# tes1.net
KiCad netlist of a schematic drawn in EAGLE
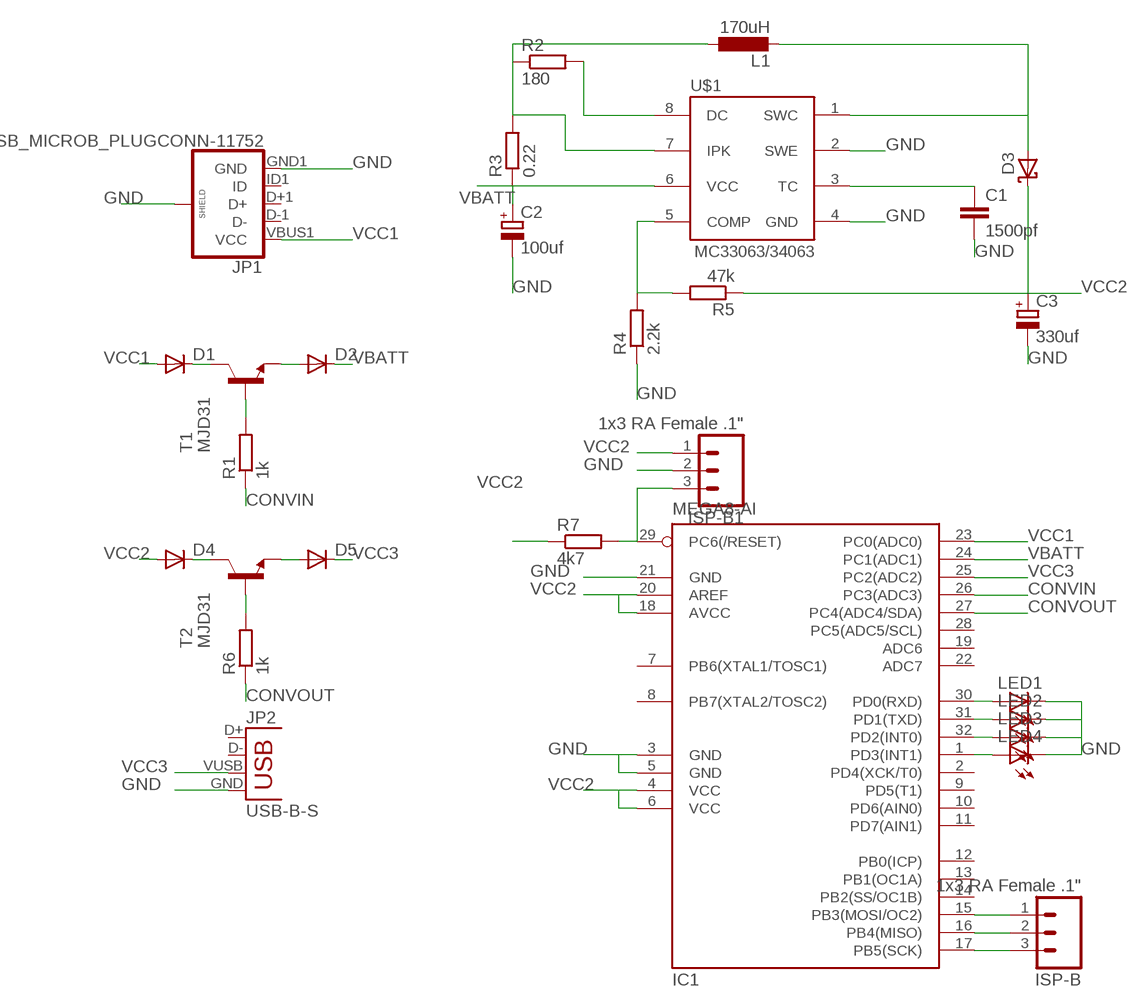
[diagram p0: schematic, sheet 1]

(export (version "E")
  (design (tool "Eeschema 10.0.6"))
  (components
    (comp (ref "C1")
      (value "1500pf")
      (footprint "eagle-import:C1206")
      (libsource (lib "eagle-import") (part "C-EUC1206"))
    )
    (comp (ref "C2")
      (value "100uf")
      (footprint "eagle-import:153CLV-1014")
      (libsource (lib "eagle-import") (part "CPOL-EU153CLV-1014"))
    )
    (comp (ref "C3")
      (value "330uf")
      (footprint "eagle-import:153CLV-1014")
      (libsource (lib "eagle-import") (part "CPOL-EU153CLV-1014"))
    )
    (comp (ref "D1")
      (value "DIODE-SMC")
      (footprint "eagle-import:SMC")
      (libsource (lib "eagle-import") (part "DIODE-SMC"))
    )
    (comp (ref "D2")
      (value "DIODE-SMC")
      (footprint "eagle-import:SMC")
      (libsource (lib "eagle-import") (part "DIODE-SMC"))
    )
    (comp (ref "D3")
      (value "SCHOTTKY-DIODEF126Z12")
      (footprint "eagle-import:F126Z12")
      (libsource (lib "eagle-import") (part "SCHOTTKY-DIODEF126Z12"))
    )
    (comp (ref "D4")
      (value "DIODE-SMC")
      (footprint "eagle-import:SMC")
      (libsource (lib "eagle-import") (part "DIODE-SMC"))
    )
    (comp (ref "D5")
      (value "DIODE-SMC")
      (footprint "eagle-import:SMC")
      (libsource (lib "eagle-import") (part "DIODE-SMC"))
    )
    (comp (ref "IC1")
      (value "MEGA8-AI")
      (footprint "eagle-import:TQFP32-08")
      (fields (field (name "MPN") "ATMEGA8-16AU"))
      (libsource (lib "eagle-import") (part "MEGA8-AI"))
    )
    (comp (ref "ISP-B")
      (value "1x3 RA Female .1\"")
      (footprint "eagle-import:1X03_SMD_RA_FEMALE")
      (libsource (lib "eagle-import") (part "M03SMD_RA_FEMALE"))
    )
    (comp (ref "ISP-B1")
      (value "1x3 RA Female .1\"")
      (footprint "eagle-import:1X03_SMD_RA_FEMALE")
      (libsource (lib "eagle-import") (part "M03SMD_RA_FEMALE"))
    )
    (comp (ref "JP1")
      (value "USB_MICROB_PLUGCONN-11752")
      (footprint "eagle-import:USB-B-MICRO-SMD_V03")
      (libsource (lib "eagle-import") (part "USB_MICROB_PLUGCONN-11752"))
    )
    (comp (ref "JP2")
      (value "USB-B-S")
      (footprint "eagle-import:USB-B-SMT")
      (libsource (lib "eagle-import") (part "USB-B-S"))
    )
    (comp (ref "L1")
      (value "170uH")
      (footprint "eagle-import:L5650M")
      (libsource (lib "eagle-import") (part "L-EUL5650M"))
    )
    (comp (ref "LED1")
      (value "LEDSML1206")
      (footprint "eagle-import:SML1206")
      (libsource (lib "eagle-import") (part "LEDSML1206"))
    )
    (comp (ref "LED2")
      (value "LEDSML1206")
      (footprint "eagle-import:SML1206")
      (libsource (lib "eagle-import") (part "LEDSML1206"))
    )
    (comp (ref "LED3")
      (value "LEDSML1206")
      (footprint "eagle-import:SML1206")
      (libsource (lib "eagle-import") (part "LEDSML1206"))
    )
    (comp (ref "LED4")
      (value "LEDSML1206")
      (footprint "eagle-import:SML1206")
      (libsource (lib "eagle-import") (part "LEDSML1206"))
    )
    (comp (ref "R1")
      (value "1k")
      (footprint "eagle-import:R1206")
      (libsource (lib "eagle-import") (part "R-EU_R1206"))
    )
    (comp (ref "R2")
      (value "180")
      (footprint "eagle-import:R1206")
      (libsource (lib "eagle-import") (part "resistor_R-EU_R1206"))
    )
    (comp (ref "R3")
      (value "0.22")
      (footprint "eagle-import:R1206")
      (libsource (lib "eagle-import") (part "resistor_R-EU_R1206"))
    )
    (comp (ref "R4")
      (value "2.2k")
      (footprint "eagle-import:R1206")
      (libsource (lib "eagle-import") (part "resistor_R-EU_R1206"))
    )
    (comp (ref "R5")
      (value "47k")
      (footprint "eagle-import:R1206")
      (libsource (lib "eagle-import") (part "resistor_R-EU_R1206"))
    )
    (comp (ref "R6")
      (value "1k")
      (footprint "eagle-import:R1206")
      (libsource (lib "eagle-import") (part "R-EU_R1206"))
    )
    (comp (ref "R7")
      (value "4k7")
      (footprint "eagle-import:R1206")
      (libsource (lib "eagle-import") (part "R-EU_R1206"))
    )
    (comp (ref "T1")
      (value "MJD31")
      (footprint "eagle-import:DPAK")
      (libsource (lib "eagle-import") (part "MJD31"))
    )
    (comp (ref "T2")
      (value "MJD31")
      (footprint "eagle-import:DPAK")
      (libsource (lib "eagle-import") (part "MJD31"))
    )
    (comp (ref "U$1")
      (value "MC33063/MC34063D")
      (footprint "eagle-import:SO08")
      (libsource (lib "eagle-import") (part "MC33063/MC34063D"))
    )
  )
  (nets
    (net (code "1") (name "/CONVIN") (class "Default")
      (node (ref "IC1") (pin "26") (pinfunction "PC3(ADC3)_26") (pintype "bidirectional"))
      (node (ref "R1") (pin "1") (pinfunction "1_1") (pintype "passive"))
    )
    (net (code "2") (name "/CONVOUT") (class "Default")
      (node (ref "IC1") (pin "27") (pinfunction "PC4(ADC4/SDA)_27") (pintype "bidirectional"))
      (node (ref "R6") (pin "1") (pinfunction "1_1") (pintype "passive"))
    )
    (net (code "3") (name "/GND") (class "Default")
      (node (ref "C1") (pin "2") (pinfunction "2_2") (pintype "passive"))
      (node (ref "C2") (pin "-") (pinfunction "-_-") (pintype "passive"))
      (node (ref "C3") (pin "-") (pinfunction "-_-") (pintype "passive"))
      (node (ref "IC1") (pin "21") (pinfunction "GND_21") (pintype "power_in"))
      (node (ref "IC1") (pin "3") (pinfunction "GND_3") (pintype "power_in"))
      (node (ref "IC1") (pin "5") (pinfunction "GND_5") (pintype "power_in"))
      (node (ref "ISP-B1") (pin "2") (pinfunction "2_2") (pintype "passive"))
      (node (ref "JP1") (pin "GND1") (pinfunction "GND_GND1") (pintype "bidirectional"))
      (node (ref "JP1") (pin "SHIELD1") (pinfunction "SHIELD_SHIELD1") (pintype "bidirectional"))
      (node (ref "JP1") (pin "SHIELD2") (pinfunction "SHIELD_SHIELD2") (pintype "bidirectional"))
      (node (ref "JP1") (pin "SHIELD3") (pinfunction "SHIELD_SHIELD3") (pintype "bidirectional"))
      (node (ref "JP2") (pin "GND") (pinfunction "GND_GND") (pintype "bidirectional"))
      (node (ref "LED1") (pin "C") (pinfunction "C_C") (pintype "passive"))
      (node (ref "LED2") (pin "C") (pinfunction "C_C") (pintype "passive"))
      (node (ref "LED3") (pin "C") (pinfunction "C_C") (pintype "passive"))
      (node (ref "LED4") (pin "C") (pinfunction "C_C") (pintype "passive"))
      (node (ref "R4") (pin "1") (pinfunction "1_1") (pintype "passive"))
      (node (ref "U$1") (pin "2") (pinfunction "SWE_2") (pintype "input"))
      (node (ref "U$1") (pin "4") (pinfunction "GND_4") (pintype "power_in"))
    )
    (net (code "4") (name "/VBATT") (class "Default")
      (node (ref "C2") (pin "+") (pinfunction "+_+") (pintype "passive"))
      (node (ref "D2") (pin "C") (pinfunction "C_C") (pintype "passive"))
      (node (ref "IC1") (pin "24") (pinfunction "PC1(ADC1)_24") (pintype "bidirectional"))
      (node (ref "R3") (pin "1") (pinfunction "1_1") (pintype "passive"))
      (node (ref "U$1") (pin "6") (pinfunction "VCC_6") (pintype "power_in"))
    )
    (net (code "5") (name "/VCC1") (class "Default")
      (node (ref "D1") (pin "A") (pinfunction "A_A") (pintype "passive"))
      (node (ref "IC1") (pin "23") (pinfunction "PC0(ADC0)_23") (pintype "bidirectional"))
      (node (ref "JP1") (pin "VBUS1") (pinfunction "VCC_VBUS1") (pintype "bidirectional"))
    )
    (net (code "6") (name "/VCC2") (class "Default")
      (node (ref "C3") (pin "+") (pinfunction "+_+") (pintype "passive"))
      (node (ref "D3") (pin "C") (pinfunction "C_C") (pintype "passive"))
      (node (ref "D4") (pin "A") (pinfunction "A_A") (pintype "passive"))
      (node (ref "IC1") (pin "18") (pinfunction "AVCC_18") (pintype "power_in"))
      (node (ref "IC1") (pin "20") (pinfunction "AREF_20") (pintype "passive"))
      (node (ref "IC1") (pin "4") (pinfunction "VCC_4") (pintype "power_in"))
      (node (ref "IC1") (pin "6") (pinfunction "VCC_6") (pintype "power_in"))
      (node (ref "ISP-B1") (pin "1") (pinfunction "1_1") (pintype "passive"))
      (node (ref "R5") (pin "1") (pinfunction "1_1") (pintype "passive"))
      (node (ref "R7") (pin "1") (pinfunction "1_1") (pintype "passive"))
    )
    (net (code "7") (name "/VCC3") (class "Default")
      (node (ref "D5") (pin "C") (pinfunction "C_C") (pintype "passive"))
      (node (ref "IC1") (pin "25") (pinfunction "PC2(ADC2)_25") (pintype "bidirectional"))
      (node (ref "JP2") (pin "VUSB") (pinfunction "VBUS_VUSB") (pintype "bidirectional"))
    )
    (net (code "8") (name "Net-(IC1-PB3(MOSI{slash}OC2))") (class "Default")
      (node (ref "IC1") (pin "15") (pinfunction "PB3(MOSI/OC2)_15") (pintype "bidirectional"))
      (node (ref "ISP-B") (pin "1") (pinfunction "1_1") (pintype "passive"))
    )
    (net (code "9") (name "Net-(IC1-PB4(MISO))") (class "Default")
      (node (ref "IC1") (pin "16") (pinfunction "PB4(MISO)_16") (pintype "bidirectional"))
      (node (ref "ISP-B") (pin "2") (pinfunction "2_2") (pintype "passive"))
    )
    (net (code "10") (name "Net-(IC1-PB5(SCK))") (class "Default")
      (node (ref "IC1") (pin "17") (pinfunction "PB5(SCK)_17") (pintype "bidirectional"))
      (node (ref "ISP-B") (pin "3") (pinfunction "3_3") (pintype "passive"))
    )
    (net (code "11") (name "Net-(IC1-PC6({slash}RESET))") (class "Default")
      (node (ref "IC1") (pin "29") (pinfunction "PC6(/RESET)_29") (pintype "bidirectional"))
      (node (ref "ISP-B1") (pin "3") (pinfunction "3_3") (pintype "passive"))
      (node (ref "R7") (pin "2") (pinfunction "2_2") (pintype "passive"))
    )
    (net (code "12") (name "Net-(IC1-PD0(RXD))") (class "Default")
      (node (ref "IC1") (pin "30") (pinfunction "PD0(RXD)_30") (pintype "bidirectional"))
      (node (ref "LED1") (pin "A") (pinfunction "A_A") (pintype "passive"))
    )
    (net (code "13") (name "Net-(IC1-PD1(TXD))") (class "Default")
      (node (ref "IC1") (pin "31") (pinfunction "PD1(TXD)_31") (pintype "bidirectional"))
      (node (ref "LED2") (pin "A") (pinfunction "A_A") (pintype "passive"))
    )
    (net (code "14") (name "Net-(IC1-PD2(INT0))") (class "Default")
      (node (ref "IC1") (pin "32") (pinfunction "PD2(INT0)_32") (pintype "bidirectional"))
      (node (ref "LED3") (pin "A") (pinfunction "A_A") (pintype "passive"))
    )
    (net (code "15") (name "Net-(IC1-PD3(INT1))") (class "Default")
      (node (ref "IC1") (pin "1") (pinfunction "PD3(INT1)_1") (pintype "bidirectional"))
      (node (ref "LED4") (pin "A") (pinfunction "A_A") (pintype "passive"))
    )
    (net (code "16") (name "Net-(T1-B)") (class "Default")
      (node (ref "R1") (pin "2") (pinfunction "2_2") (pintype "passive"))
      (node (ref "T1") (pin "1") (pinfunction "B_1") (pintype "passive"))
    )
    (net (code "17") (name "Net-(T1-C)") (class "Default")
      (node (ref "D1") (pin "C") (pinfunction "C_C") (pintype "passive"))
      (node (ref "T1") (pin "4") (pinfunction "C_4") (pintype "passive"))
    )
    (net (code "18") (name "Net-(T1-E)") (class "Default")
      (node (ref "D2") (pin "A") (pinfunction "A_A") (pintype "passive"))
      (node (ref "T1") (pin "3") (pinfunction "E_3") (pintype "passive"))
    )
    (net (code "19") (name "Net-(T2-B)") (class "Default")
      (node (ref "R6") (pin "2") (pinfunction "2_2") (pintype "passive"))
      (node (ref "T2") (pin "1") (pinfunction "B_1") (pintype "passive"))
    )
    (net (code "20") (name "Net-(T2-C)") (class "Default")
      (node (ref "D4") (pin "C") (pinfunction "C_C") (pintype "passive"))
      (node (ref "T2") (pin "4") (pinfunction "C_4") (pintype "passive"))
    )
    (net (code "21") (name "Net-(T2-E)") (class "Default")
      (node (ref "D5") (pin "A") (pinfunction "A_A") (pintype "passive"))
      (node (ref "T2") (pin "3") (pinfunction "E_3") (pintype "passive"))
    )
    (net (code "22") (name "Net-(U$1-COMP)") (class "Default")
      (node (ref "R4") (pin "2") (pinfunction "2_2") (pintype "passive"))
      (node (ref "R5") (pin "2") (pinfunction "2_2") (pintype "passive"))
      (node (ref "U$1") (pin "5") (pinfunction "COMP_5") (pintype "input"))
    )
    (net (code "23") (name "Net-(U$1-DC)") (class "Default")
      (node (ref "R2") (pin "2") (pinfunction "2_2") (pintype "passive"))
      (node (ref "U$1") (pin "8") (pinfunction "DC_8") (pintype "input"))
    )
    (net (code "24") (name "Net-(U$1-IPK)") (class "Default")
      (node (ref "L1") (pin "1") (pinfunction "1_1") (pintype "passive"))
      (node (ref "R2") (pin "1") (pinfunction "1_1") (pintype "passive"))
      (node (ref "R3") (pin "2") (pinfunction "2_2") (pintype "passive"))
      (node (ref "U$1") (pin "7") (pinfunction "IPK_7") (pintype "bidirectional"))
    )
    (net (code "25") (name "Net-(U$1-SWC)") (class "Default")
      (node (ref "D3") (pin "A") (pinfunction "A_A") (pintype "passive"))
      (node (ref "L1") (pin "2") (pinfunction "2_2") (pintype "passive"))
      (node (ref "U$1") (pin "1") (pinfunction "SWC_1") (pintype "input"))
    )
    (net (code "26") (name "Net-(U$1-TC)") (class "Default")
      (node (ref "C1") (pin "1") (pinfunction "1_1") (pintype "passive"))
      (node (ref "U$1") (pin "3") (pinfunction "TC_3") (pintype "input"))
    )
    (net (code "27") (name "unconnected-(IC1-ADC6-Pad19)") (class "Default")
      (node (ref "IC1") (pin "19") (pinfunction "ADC6_19") (pintype "bidirectional"))
    )
    (net (code "28") (name "unconnected-(IC1-ADC7-Pad22)") (class "Default")
      (node (ref "IC1") (pin "22") (pinfunction "ADC7_22") (pintype "bidirectional"))
    )
    (net (code "29") (name "unconnected-(IC1-PB0(ICP)-Pad12)") (class "Default")
      (node (ref "IC1") (pin "12") (pinfunction "PB0(ICP)_12") (pintype "bidirectional"))
    )
    (net (code "30") (name "unconnected-(IC1-PB1(OC1A)-Pad13)") (class "Default")
      (node (ref "IC1") (pin "13") (pinfunction "PB1(OC1A)_13") (pintype "bidirectional"))
    )
    (net (code "31") (name "unconnected-(IC1-PB2(SS{slash}OC1B)-Pad14)") (class "Default")
      (node (ref "IC1") (pin "14") (pinfunction "PB2(SS/OC1B)_14") (pintype "bidirectional"))
    )
    (net (code "32") (name "unconnected-(IC1-PB6(XTAL1{slash}TOSC1)-Pad7)") (class "Default")
      (node (ref "IC1") (pin "7") (pinfunction "PB6(XTAL1/TOSC1)_7") (pintype "bidirectional"))
    )
    (net (code "33") (name "unconnected-(IC1-PB7(XTAL2{slash}TOSC2)-Pad8)") (class "Default")
      (node (ref "IC1") (pin "8") (pinfunction "PB7(XTAL2/TOSC2)_8") (pintype "bidirectional"))
    )
    (net (code "34") (name "unconnected-(IC1-PC5(ADC5{slash}SCL)-Pad28)") (class "Default")
      (node (ref "IC1") (pin "28") (pinfunction "PC5(ADC5/SCL)_28") (pintype "bidirectional"))
    )
    (net (code "35") (name "unconnected-(IC1-PD4(XCK{slash}T0)-Pad2)") (class "Default")
      (node (ref "IC1") (pin "2") (pinfunction "PD4(XCK/T0)_2") (pintype "bidirectional"))
    )
    (net (code "36") (name "unconnected-(IC1-PD5(T1)-Pad9)") (class "Default")
      (node (ref "IC1") (pin "9") (pinfunction "PD5(T1)_9") (pintype "bidirectional"))
    )
    (net (code "37") (name "unconnected-(IC1-PD6(AIN0)-Pad10)") (class "Default")
      (node (ref "IC1") (pin "10") (pinfunction "PD6(AIN0)_10") (pintype "bidirectional"))
    )
    (net (code "38") (name "unconnected-(IC1-PD7(AIN1)-Pad11)") (class "Default")
      (node (ref "IC1") (pin "11") (pinfunction "PD7(AIN1)_11") (pintype "bidirectional"))
    )
    (net (code "39") (name "unconnected-(JP1-D+-PadD+1)") (class "Default")
      (node (ref "JP1") (pin "D+1") (pinfunction "D+_D+1") (pintype "bidirectional"))
    )
    (net (code "40") (name "unconnected-(JP1-D--PadD-1)") (class "Default")
      (node (ref "JP1") (pin "D-1") (pinfunction "D-_D-1") (pintype "bidirectional"))
    )
    (net (code "41") (name "unconnected-(JP1-ID-PadID1)") (class "Default")
      (node (ref "JP1") (pin "ID1") (pinfunction "ID_ID1") (pintype "bidirectional"))
    )
    (net (code "42") (name "unconnected-(JP2-PadD+)") (class "Default")
      (node (ref "JP2") (pin "D+") (pinfunction "D+_D+") (pintype "bidirectional"))
    )
    (net (code "43") (name "unconnected-(JP2-PadD-)") (class "Default")
      (node (ref "JP2") (pin "D-") (pinfunction "D-_D-") (pintype "bidirectional"))
    )
  )
)
